# BMS-S05-V01-Isolation.net
KiCad netlist of a schematic drawn in Altium Designer
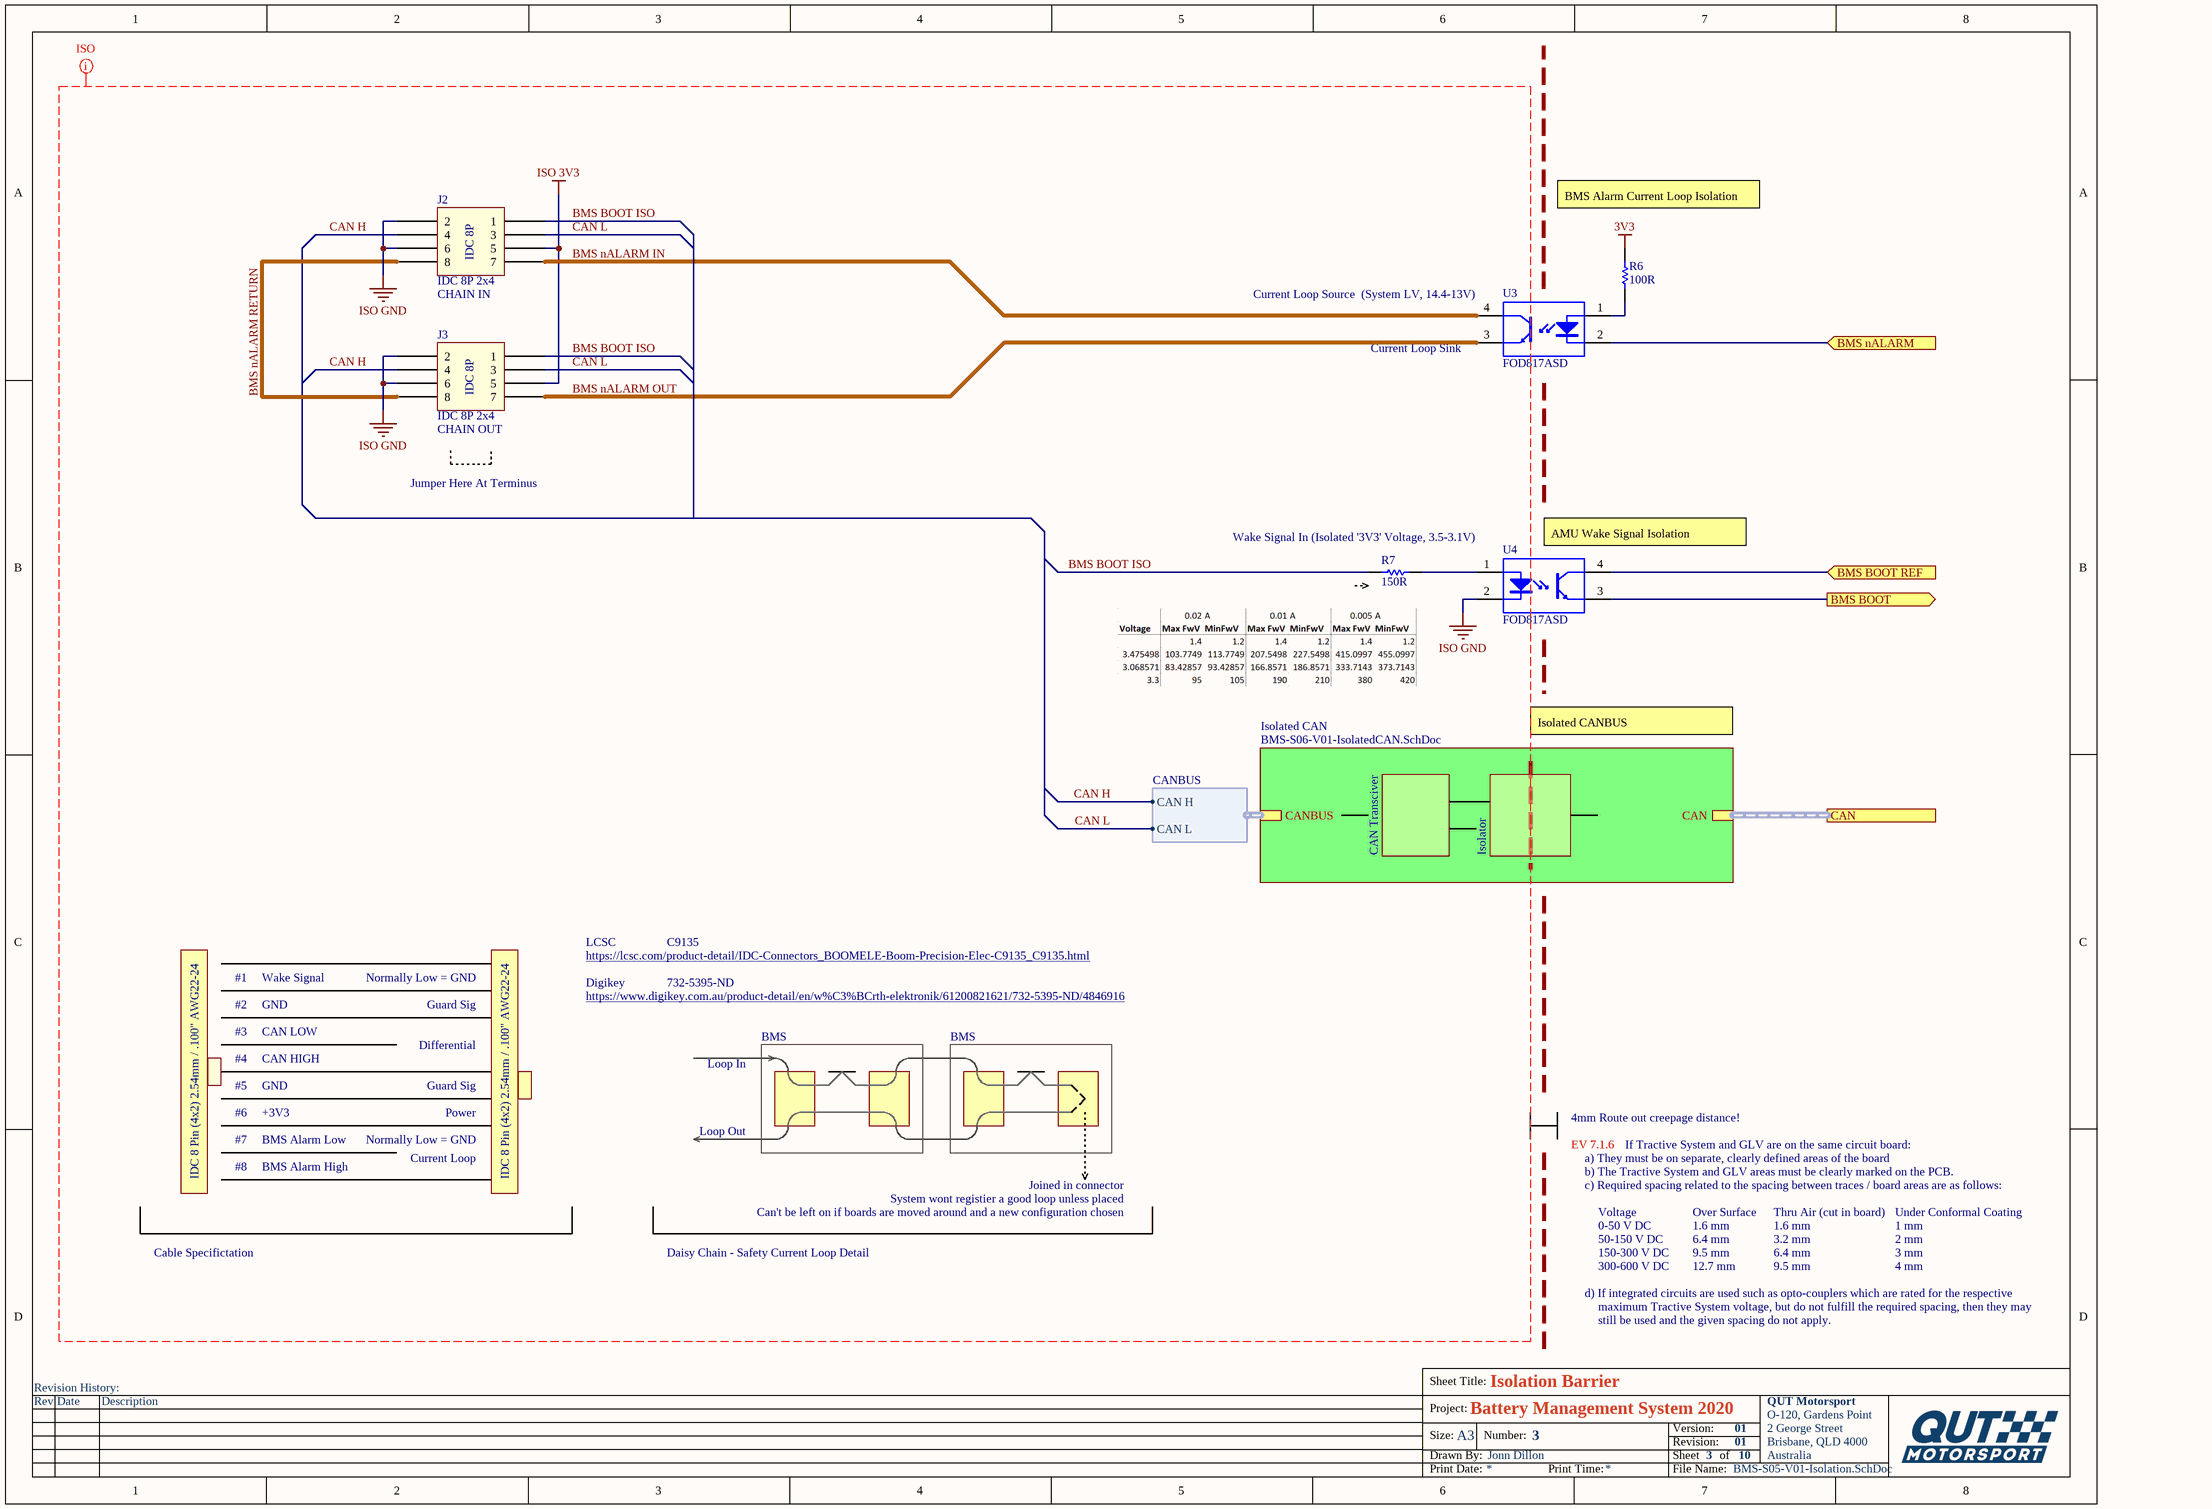
[diagram p0: BMS-S05-V01-Isolation.SchDoc]

(export (version "E")
  (design (tool "Eeschema 10.0.6"))
  (components
    (comp (ref "J2")
      (value "IDC 8P 2x4")
      (footprint "IDC 2.54MM 8P")
      (description "IDC 8P 2x5")
      (libsource (lib "IDCConnectors") (part "IDC 8P 2x4"))
    )
    (comp (ref "J3")
      (value "IDC 8P 2x4")
      (footprint "IDC 2.54MM 8P")
      (description "IDC 8P 2x5")
      (libsource (lib "IDCConnectors") (part "IDC 8P 2x4"))
    )
    (comp (ref "R6")
      (value "100R")
      (footprint "Res_ThinFilm_0603")
      (description "Resistor, SMD, 100R, 0.1W, 5%, 0603")
      (libsource (lib "StandardResistors") (part "100R 5%, 0603"))
    )
    (comp (ref "R7")
      (value "150R")
      (footprint "Res_ThinFilm_0603")
      (description "Resistor, SMD, 150R, 0.1W, 5%, 0603")
      (libsource (lib "StandardResistors") (part "150R 5% 0603"))
    )
    (comp (ref "U3")
      (value "FOD817ASD")
      (footprint "FOD817ASD")
      (description "Optoisolator 5kV Transistor 4SMD")
      (libsource (lib "QUTMS_OctocouplerLibrary") (part "FOD817ASD"))
    )
    (comp (ref "U4")
      (value "FOD817ASD")
      (footprint "FOD817ASD")
      (description "Optoisolator 5kV Transistor 4SMD")
      (libsource (lib "QUTMS_OctocouplerLibrary") (part "FOD817ASD"))
    )
  )
  (nets
    (net (code "3") (name "/BMS BOOT") (class "Default")
      (node (ref "U4") (pin "3") (pinfunction "EMITTER_3") (pintype "passive"))
    )
    (net (code "4") (name "/BMS BOOT ISO") (class "Default")
      (node (ref "J2") (pin "1") (pinfunction "1_1") (pintype "passive"))
      (node (ref "J3") (pin "1") (pinfunction "1_1") (pintype "passive"))
      (node (ref "R7") (pin "1") (pinfunction "1_1") (pintype "passive"))
    )
    (net (code "5") (name "/BMS BOOT REF") (class "Default")
      (node (ref "U4") (pin "4") (pinfunction "COLLECTOR_4") (pintype "passive"))
    )
    (net (code "6") (name "/BMS nALARM") (class "Default")
      (node (ref "U3") (pin "2") (pinfunction "CATHODE_2") (pintype "passive"))
    )
    (net (code "7") (name "/BMS nALARM IN") (class "Default")
      (node (ref "J2") (pin "7") (pinfunction "7_7") (pintype "passive"))
      (node (ref "U3") (pin "4") (pinfunction "COLLECTOR_4") (pintype "passive"))
    )
    (net (code "8") (name "/BMS nALARM OUT") (class "Default")
      (node (ref "J3") (pin "7") (pinfunction "7_7") (pintype "passive"))
      (node (ref "U3") (pin "3") (pinfunction "EMITTER_3") (pintype "passive"))
    )
    (net (code "9") (name "/BMS nALARM RETURN") (class "Default")
      (node (ref "J2") (pin "8") (pinfunction "8_8") (pintype "passive"))
      (node (ref "J3") (pin "8") (pinfunction "8_8") (pintype "passive"))
    )
    (net (code "10") (name "/CAN H") (class "Default")
      (node (ref "J2") (pin "4") (pinfunction "4_4") (pintype "passive"))
      (node (ref "J3") (pin "4") (pinfunction "4_4") (pintype "passive"))
    )
    (net (code "11") (name "/CAN L") (class "Default")
      (node (ref "J2") (pin "3") (pinfunction "3_3") (pintype "passive"))
      (node (ref "J3") (pin "3") (pinfunction "3_3") (pintype "passive"))
    )
    (net (code "14") (name "3V3") (class "Default")
      (node (ref "R6") (pin "2") (pinfunction "2_2") (pintype "passive"))
    )
    (net (code "15") (name "ISO 3V3") (class "Default")
      (node (ref "J2") (pin "5") (pinfunction "5_5") (pintype "passive"))
      (node (ref "J3") (pin "5") (pinfunction "5_5") (pintype "passive"))
    )
    (net (code "16") (name "ISO GND") (class "Default")
      (node (ref "J2") (pin "2") (pinfunction "2_2") (pintype "passive"))
      (node (ref "J2") (pin "6") (pinfunction "6_6") (pintype "passive"))
      (node (ref "J3") (pin "2") (pinfunction "2_2") (pintype "passive"))
      (node (ref "J3") (pin "6") (pinfunction "6_6") (pintype "passive"))
      (node (ref "U4") (pin "2") (pinfunction "CATHODE_2") (pintype "passive"))
    )
    (net (code "17") (name "Net-(U3-ANODE)") (class "Default")
      (node (ref "R6") (pin "1") (pinfunction "1_1") (pintype "passive"))
      (node (ref "U3") (pin "1") (pinfunction "ANODE_1") (pintype "passive"))
    )
    (net (code "18") (name "Net-(U4-ANODE)") (class "Default")
      (node (ref "R7") (pin "2") (pinfunction "2_2") (pintype "passive"))
      (node (ref "U4") (pin "1") (pinfunction "ANODE_1") (pintype "passive"))
    )
  )
)
